# Monitoring_System_schematics.net
KiCad netlist of a schematic drawn in EasyEDA
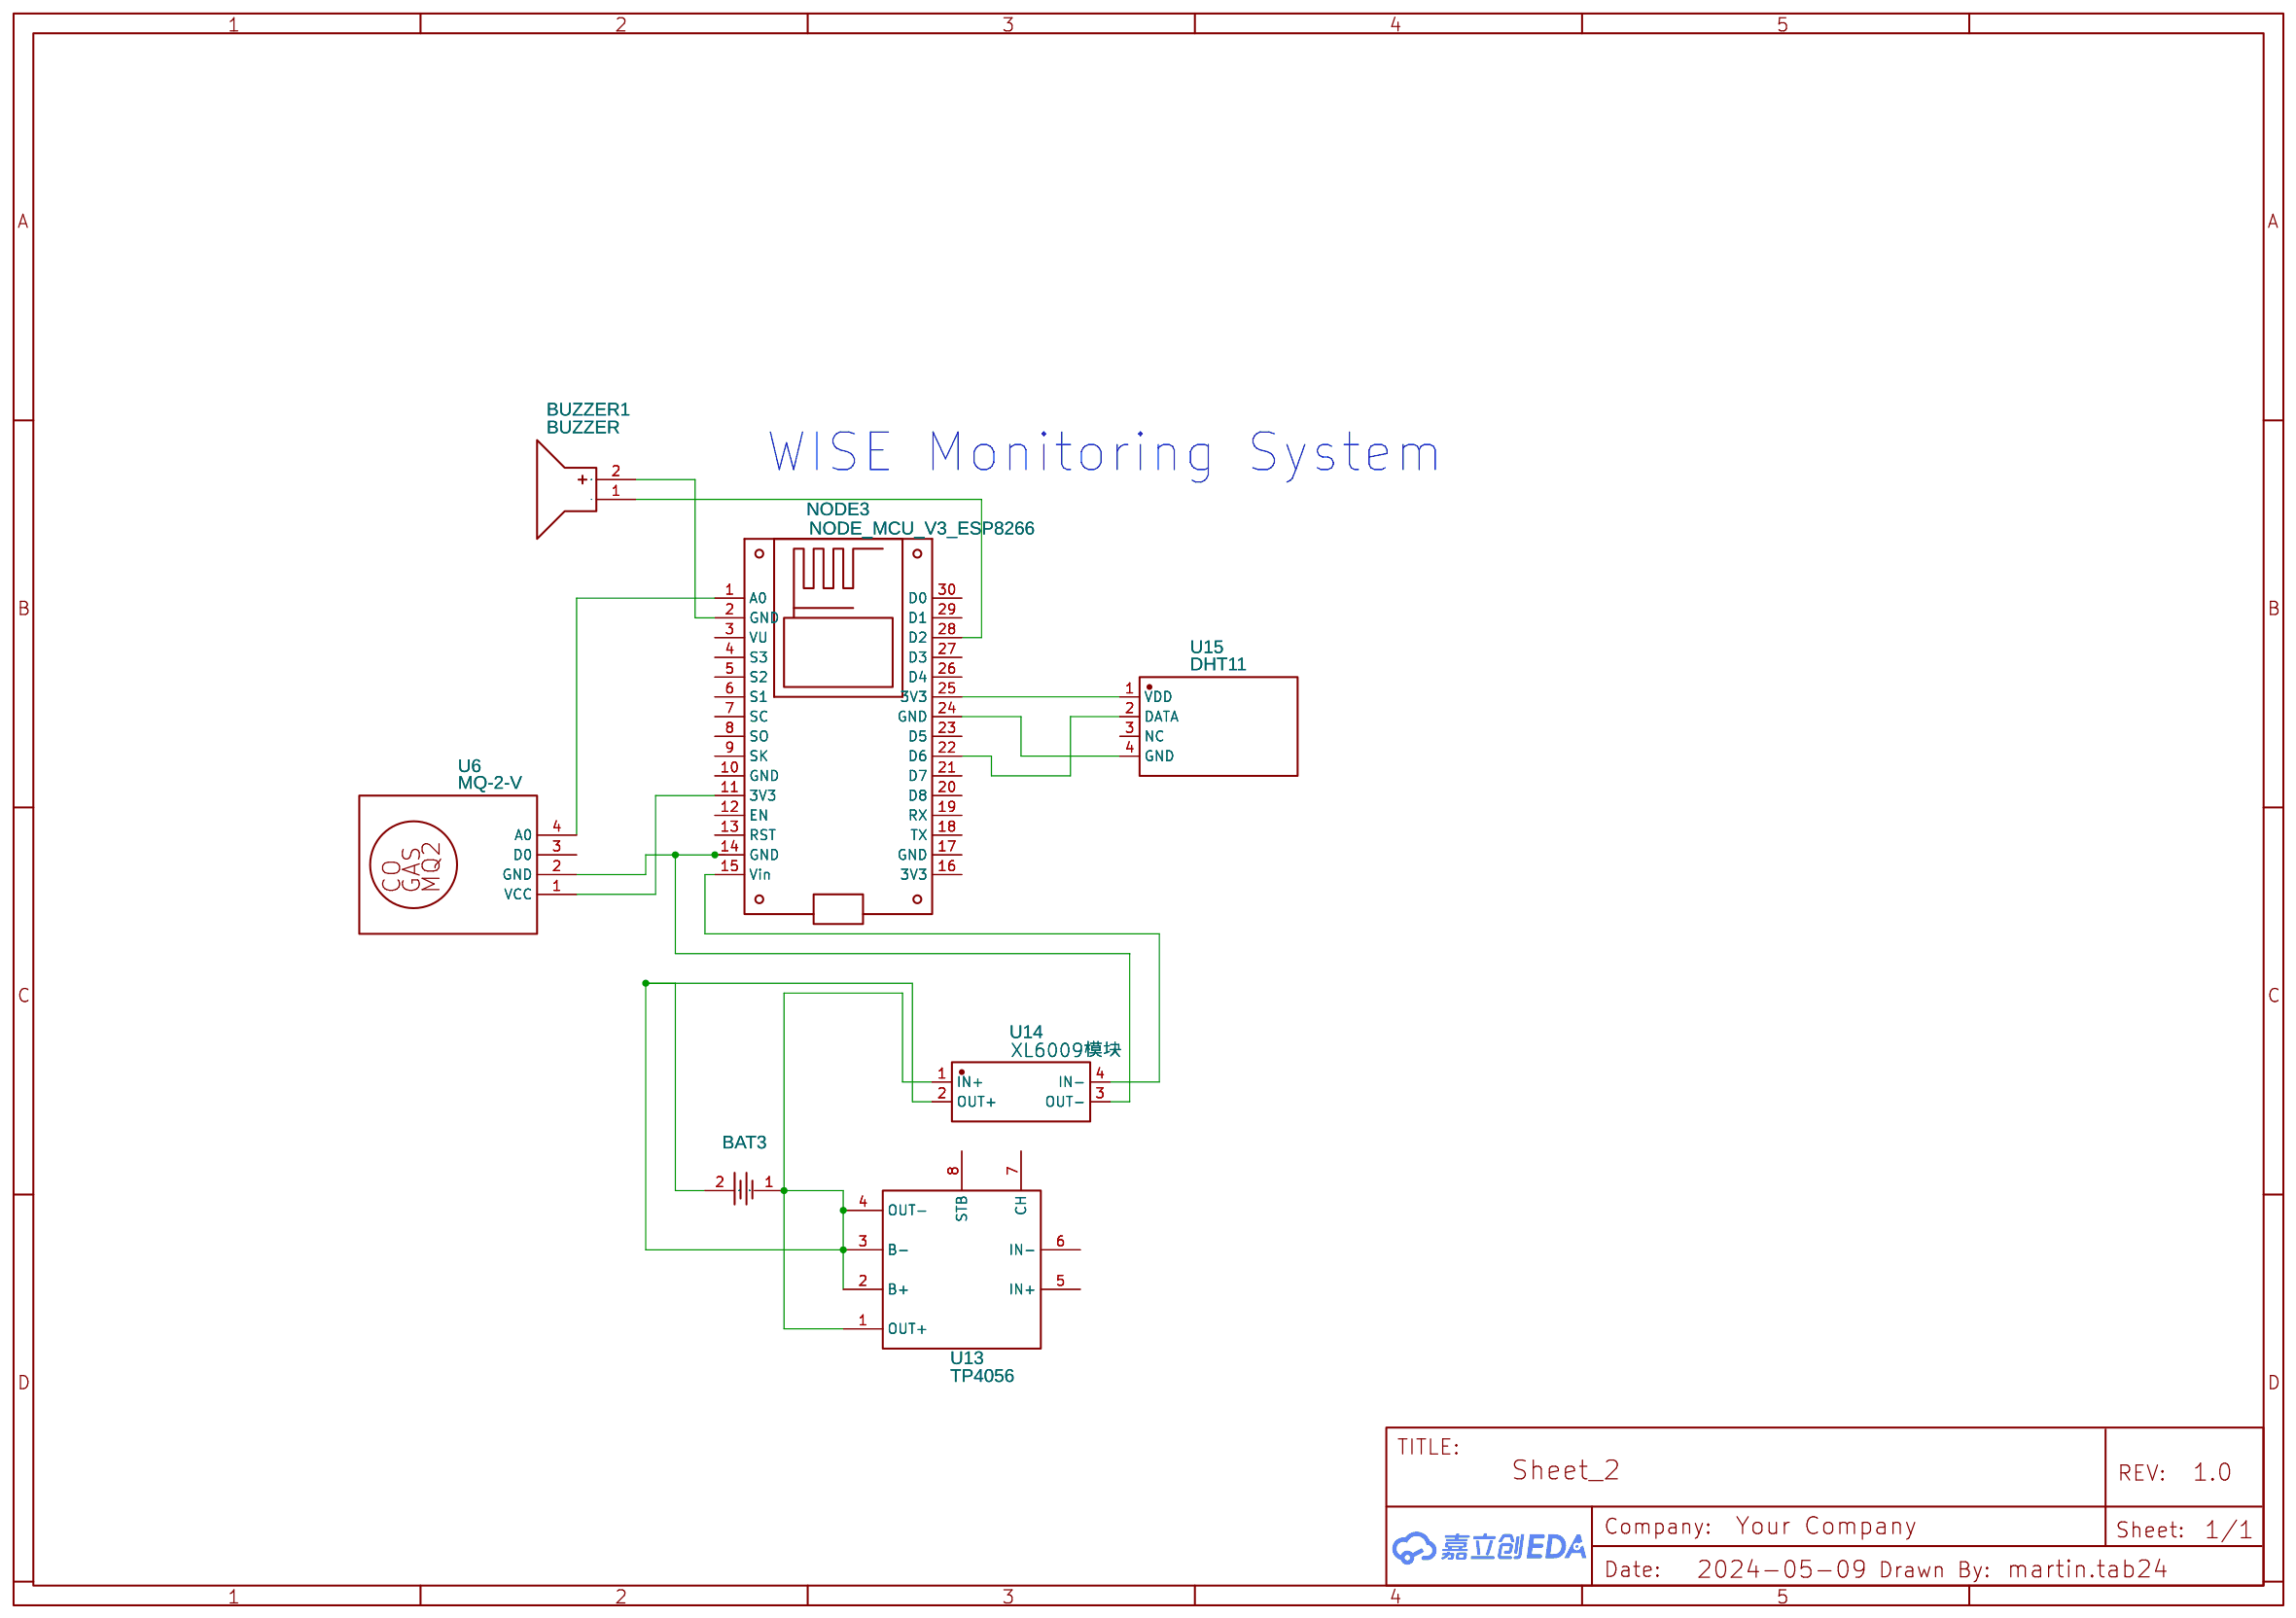
[diagram p0: schematic sheet]

(export (version "E")
  (design (tool "Eeschema 10.0.6"))
  (components
    (comp (ref "BAT3")
      (value "BH-18650-B6AA002")
      (fields (field (name "Manufacturer") "MYOUNG(美阳)"))
      (libsource (lib "") (part "BH-18650-B6AA002"))
    )
    (comp (ref "BUZZER1")
      (value "BUZZER")
      (fields (field (name "Manufacturer Part") "buzzer"))
      (libsource (lib "") (part "BUZZER"))
    )
    (comp (ref "NODE3") (value "NODE_MCU_V3_ESP8266") (libsource (lib "") (part "NODE_MCU_V3_ESP8266")))
    (comp (ref "U6")
      (value "MQ-2-V")
      (fields (field (name "Manufacturer") "Flying Fish"))
      (libsource (lib "") (part "MQ-2-V"))
    )
    (comp (ref "U13")
      (value "TP4056")
      (fields (field (name "BOM_Manufacturer Part") "New SchematicLib"))
      (libsource (lib "") (part "TP4056"))
    )
    (comp (ref "U14")
      (value "XL6009模块")
      (fields (field (name "Manufacturer Part") "xl6009模块"))
      (libsource (lib "") (part "XL6009模块"))
    )
    (comp (ref "U15")
      (value "DHT11")
      (fields (field (name "Manufacturer") "广州奥松"))
      (libsource (lib "") (part "DHT11"))
    )
  )
  (nets
    (net (code "1") (name "Net-(BUZZER1-+)") (class "Default")
      (node (ref "BUZZER1") (pin "2") (pinfunction "+_2") (pintype "unspecified"))
      (node (ref "NODE3") (pin "2") (pinfunction "GND_2") (pintype "unspecified"))
    )
    (net (code "2") (name "Net-(BUZZER1--)") (class "Default")
      (node (ref "BUZZER1") (pin "1") (pinfunction "-_1") (pintype "unspecified"))
      (node (ref "NODE3") (pin "28") (pinfunction "D2_28") (pintype "unspecified"))
    )
    (net (code "3") (name "Net-(NODE3-A0)") (class "Default")
      (node (ref "NODE3") (pin "1") (pinfunction "A0_1") (pintype "unspecified"))
      (node (ref "U6") (pin "4") (pinfunction "A0_4") (pintype "input"))
    )
    (net (code "4") (name "Net-(NODE3-D6)") (class "Default")
      (node (ref "NODE3") (pin "22") (pinfunction "D6_22") (pintype "unspecified"))
      (node (ref "U15") (pin "2") (pinfunction "DATA_2") (pintype "unspecified"))
    )
    (net (code "5") (name "Net-(NODE3-Vin)") (class "Default")
      (node (ref "NODE3") (pin "15") (pinfunction "Vin_15") (pintype "unspecified"))
      (node (ref "U14") (pin "4") (pinfunction "IN-_4") (pintype "unspecified"))
    )
    (net (code "6") (name "Net-(U6-VCC)") (class "Default")
      (node (ref "NODE3") (pin "11") (pinfunction "3V3_11") (pintype "unspecified"))
      (node (ref "U6") (pin "1") (pinfunction "VCC_1") (pintype "passive"))
    )
    (net (code "7") (name "Net-(U13-B+)") (class "Default")
      (node (ref "BAT3") (pin "1") (pinfunction "1_1") (pintype "input"))
      (node (ref "BAT3") (pin "2") (pinfunction "2_2") (pintype "input"))
      (node (ref "U13") (pin "1") (pinfunction "OUT+_1") (pintype "unspecified"))
      (node (ref "U13") (pin "2") (pinfunction "B+_2") (pintype "unspecified"))
      (node (ref "U13") (pin "3") (pinfunction "B-_3") (pintype "unspecified"))
      (node (ref "U13") (pin "4") (pinfunction "OUT-_4") (pintype "unspecified"))
      (node (ref "U14") (pin "1") (pinfunction "IN+_1") (pintype "unspecified"))
      (node (ref "U14") (pin "2") (pinfunction "OUT+_2") (pintype "unspecified"))
    )
    (net (code "8") (name "Net-(U14-OUT-)") (class "Default")
      (node (ref "NODE3") (pin "14") (pinfunction "GND_14") (pintype "unspecified"))
      (node (ref "U14") (pin "3") (pinfunction "OUT-_3") (pintype "unspecified"))
      (node (ref "U6") (pin "2") (pinfunction "GND_2") (pintype "passive"))
    )
    (net (code "9") (name "Net-(U15-GND)") (class "Default")
      (node (ref "NODE3") (pin "24") (pinfunction "GND_24") (pintype "unspecified"))
      (node (ref "U15") (pin "4") (pinfunction "GND_4") (pintype "unspecified"))
    )
    (net (code "10") (name "Net-(U15-VDD)") (class "Default")
      (node (ref "NODE3") (pin "25") (pinfunction "3V3_25") (pintype "unspecified"))
      (node (ref "U15") (pin "1") (pinfunction "VDD_1") (pintype "unspecified"))
    )
    (net (code "11") (name "unconnected-(NODE3-3V3-Pad16)") (class "Default")
      (node (ref "NODE3") (pin "16") (pinfunction "3V3_16") (pintype "unspecified"))
    )
    (net (code "12") (name "unconnected-(NODE3-D0-Pad30)") (class "Default")
      (node (ref "NODE3") (pin "30") (pinfunction "D0_30") (pintype "unspecified"))
    )
    (net (code "13") (name "unconnected-(NODE3-D1-Pad29)") (class "Default")
      (node (ref "NODE3") (pin "29") (pinfunction "D1_29") (pintype "unspecified"))
    )
    (net (code "14") (name "unconnected-(NODE3-D3-Pad27)") (class "Default")
      (node (ref "NODE3") (pin "27") (pinfunction "D3_27") (pintype "unspecified"))
    )
    (net (code "15") (name "unconnected-(NODE3-D4-Pad26)") (class "Default")
      (node (ref "NODE3") (pin "26") (pinfunction "D4_26") (pintype "unspecified"))
    )
    (net (code "16") (name "unconnected-(NODE3-D5-Pad23)") (class "Default")
      (node (ref "NODE3") (pin "23") (pinfunction "D5_23") (pintype "unspecified"))
    )
    (net (code "17") (name "unconnected-(NODE3-D7-Pad21)") (class "Default")
      (node (ref "NODE3") (pin "21") (pinfunction "D7_21") (pintype "unspecified"))
    )
    (net (code "18") (name "unconnected-(NODE3-D8-Pad20)") (class "Default")
      (node (ref "NODE3") (pin "20") (pinfunction "D8_20") (pintype "unspecified"))
    )
    (net (code "19") (name "unconnected-(NODE3-EN-Pad12)") (class "Default")
      (node (ref "NODE3") (pin "12") (pinfunction "EN_12") (pintype "unspecified"))
    )
    (net (code "20") (name "unconnected-(NODE3-GND-Pad10)") (class "Default")
      (node (ref "NODE3") (pin "10") (pinfunction "GND_10") (pintype "unspecified"))
    )
    (net (code "21") (name "unconnected-(NODE3-GND-Pad17)") (class "Default")
      (node (ref "NODE3") (pin "17") (pinfunction "GND_17") (pintype "unspecified"))
    )
    (net (code "22") (name "unconnected-(NODE3-RST-Pad13)") (class "Default")
      (node (ref "NODE3") (pin "13") (pinfunction "RST_13") (pintype "unspecified"))
    )
    (net (code "23") (name "unconnected-(NODE3-RX-Pad19)") (class "Default")
      (node (ref "NODE3") (pin "19") (pinfunction "RX_19") (pintype "unspecified"))
    )
    (net (code "24") (name "unconnected-(NODE3-S1-Pad6)") (class "Default")
      (node (ref "NODE3") (pin "6") (pinfunction "S1_6") (pintype "unspecified"))
    )
    (net (code "25") (name "unconnected-(NODE3-S2-Pad5)") (class "Default")
      (node (ref "NODE3") (pin "5") (pinfunction "S2_5") (pintype "unspecified"))
    )
    (net (code "26") (name "unconnected-(NODE3-S3-Pad4)") (class "Default")
      (node (ref "NODE3") (pin "4") (pinfunction "S3_4") (pintype "unspecified"))
    )
    (net (code "27") (name "unconnected-(NODE3-SC-Pad7)") (class "Default")
      (node (ref "NODE3") (pin "7") (pinfunction "SC_7") (pintype "unspecified"))
    )
    (net (code "28") (name "unconnected-(NODE3-SK-Pad9)") (class "Default")
      (node (ref "NODE3") (pin "9") (pinfunction "SK_9") (pintype "unspecified"))
    )
    (net (code "29") (name "unconnected-(NODE3-SO-Pad8)") (class "Default")
      (node (ref "NODE3") (pin "8") (pinfunction "SO_8") (pintype "unspecified"))
    )
    (net (code "30") (name "unconnected-(NODE3-TX-Pad18)") (class "Default")
      (node (ref "NODE3") (pin "18") (pinfunction "TX_18") (pintype "unspecified"))
    )
    (net (code "31") (name "unconnected-(NODE3-VU-Pad3)") (class "Default")
      (node (ref "NODE3") (pin "3") (pinfunction "VU_3") (pintype "unspecified"))
    )
    (net (code "32") (name "unconnected-(U6-D0-Pad3)") (class "Default")
      (node (ref "U6") (pin "3") (pinfunction "D0_3") (pintype "output"))
    )
    (net (code "33") (name "unconnected-(U13-CH-Pad7)") (class "Default")
      (node (ref "U13") (pin "7") (pinfunction "CH_7") (pintype "unspecified"))
    )
    (net (code "34") (name "unconnected-(U13-IN+-Pad5)") (class "Default")
      (node (ref "U13") (pin "5") (pinfunction "IN+_5") (pintype "unspecified"))
    )
    (net (code "35") (name "unconnected-(U13-IN--Pad6)") (class "Default")
      (node (ref "U13") (pin "6") (pinfunction "IN-_6") (pintype "unspecified"))
    )
    (net (code "36") (name "unconnected-(U13-STB-Pad8)") (class "Default")
      (node (ref "U13") (pin "8") (pinfunction "STB_8") (pintype "unspecified"))
    )
    (net (code "37") (name "unconnected-(U15-NC-Pad3)") (class "Default")
      (node (ref "U15") (pin "3") (pinfunction "NC_3") (pintype "unspecified"))
    )
  )
)
